# 05_RS485.net
KiCad netlist of a schematic drawn in Altium Designer
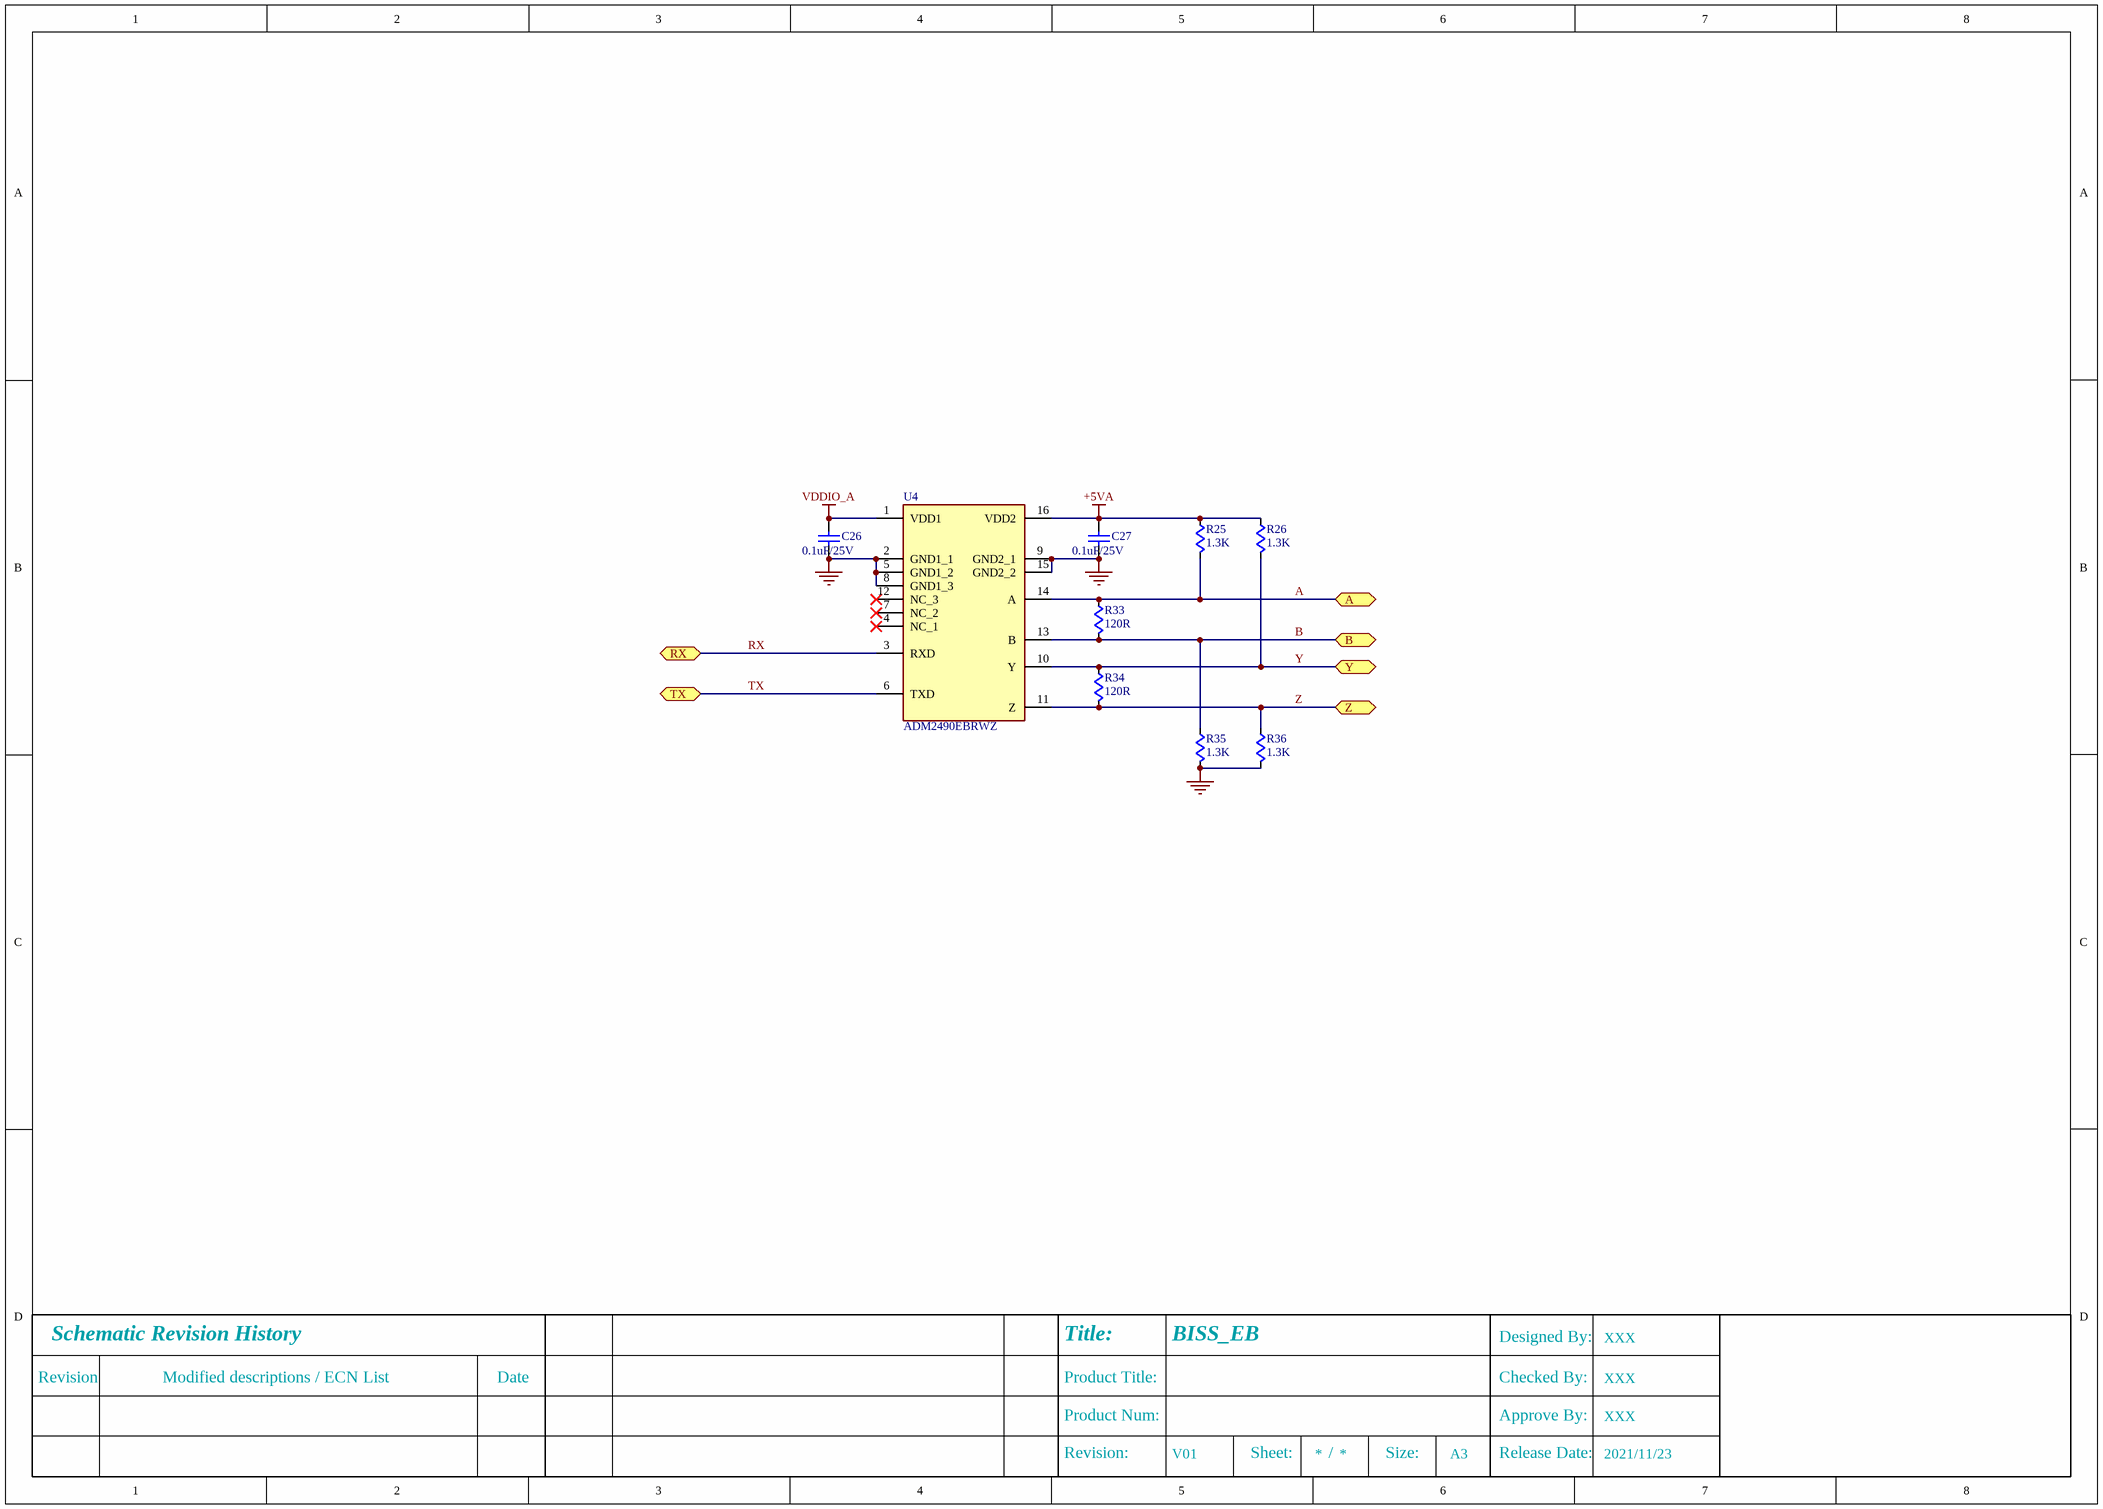
[diagram p0: 05_RS485.SchDoc]

(export (version "E")
  (design (tool "Eeschema 10.0.6"))
  (components
    (comp (ref "C26")
      (value "0.1uF/25V")
      (footprint "C0603")
      (description "MLCC")
      (libsource (lib "SamacSys") (part "C"))
    )
    (comp (ref "C27")
      (value "0.1uF/25V")
      (footprint "C0603")
      (description "MLCC")
      (libsource (lib "SamacSys") (part "C"))
    )
    (comp (ref "R25")
      (value "1.3K")
      (footprint "SamacSys:R0603")
      (description "贴片电阻")
      (libsource (lib "SamacSys") (part "R"))
    )
    (comp (ref "R26")
      (value "1.3K")
      (footprint "SamacSys:R0603")
      (description "贴片电阻")
      (libsource (lib "SamacSys") (part "R"))
    )
    (comp (ref "R33")
      (value "120R")
      (footprint "SamacSys:R0603")
      (description "贴片电阻")
      (libsource (lib "SamacSys") (part "R"))
    )
    (comp (ref "R34")
      (value "120R")
      (footprint "SamacSys:R0603")
      (description "贴片电阻")
      (libsource (lib "SamacSys") (part "R"))
    )
    (comp (ref "R35")
      (value "1.3K")
      (footprint "SamacSys:R0603")
      (description "贴片电阻")
      (libsource (lib "SamacSys") (part "R"))
    )
    (comp (ref "R36")
      (value "1.3K")
      (footprint "SamacSys:R0603")
      (description "贴片电阻")
      (libsource (lib "SamacSys") (part "R"))
    )
    (comp (ref "U4")
      (value "ADM2490EBRWZ")
      (footprint "SamacSys:SOIC127P1032X265-16N")
      (description "Integrated Circuit")
      (fields (field (name "MOUSER PART NUMBER") "584-ADM2490EBRWZ"))
      (libsource (lib "SamacSys") (part "ADM2490EBRWZ"))
    )
  )
  (nets
    (net (code "1") (name "+5VA") (class "Default")
      (node (ref "C27") (pin "1") (pinfunction "1_1") (pintype "passive"))
      (node (ref "R25") (pin "1") (pinfunction "1_1") (pintype "passive"))
      (node (ref "R26") (pin "1") (pinfunction "1_1") (pintype "passive"))
      (node (ref "U4") (pin "16") (pinfunction "VDD2_16") (pintype "passive"))
    )
    (net (code "2") (name "/A") (class "Default")
      (node (ref "R25") (pin "2") (pinfunction "2_2") (pintype "passive"))
      (node (ref "R33") (pin "1") (pinfunction "1_1") (pintype "passive"))
      (node (ref "U4") (pin "14") (pinfunction "A_14") (pintype "passive"))
    )
    (net (code "3") (name "/B") (class "Default")
      (node (ref "R33") (pin "2") (pinfunction "2_2") (pintype "passive"))
      (node (ref "R35") (pin "1") (pinfunction "1_1") (pintype "passive"))
      (node (ref "U4") (pin "13") (pinfunction "B_13") (pintype "passive"))
    )
    (net (code "4") (name "/RX") (class "Default")
      (node (ref "U4") (pin "3") (pinfunction "RXD_3") (pintype "passive"))
    )
    (net (code "5") (name "/TX") (class "Default")
      (node (ref "U4") (pin "6") (pinfunction "TXD_6") (pintype "passive"))
    )
    (net (code "6") (name "/Y") (class "Default")
      (node (ref "R26") (pin "2") (pinfunction "2_2") (pintype "passive"))
      (node (ref "R34") (pin "1") (pinfunction "1_1") (pintype "passive"))
      (node (ref "U4") (pin "10") (pinfunction "Y_10") (pintype "passive"))
    )
    (net (code "7") (name "/Z") (class "Default")
      (node (ref "R34") (pin "2") (pinfunction "2_2") (pintype "passive"))
      (node (ref "R36") (pin "1") (pinfunction "1_1") (pintype "passive"))
      (node (ref "U4") (pin "11") (pinfunction "Z_11") (pintype "passive"))
    )
    (net (code "8") (name "GND") (class "Default")
      (node (ref "C26") (pin "2") (pinfunction "2_2") (pintype "passive"))
      (node (ref "C27") (pin "2") (pinfunction "2_2") (pintype "passive"))
      (node (ref "R35") (pin "2") (pinfunction "2_2") (pintype "passive"))
      (node (ref "R36") (pin "2") (pinfunction "2_2") (pintype "passive"))
      (node (ref "U4") (pin "15") (pinfunction "GND2_2_15") (pintype "passive"))
      (node (ref "U4") (pin "2") (pinfunction "GND1_1_2") (pintype "passive"))
      (node (ref "U4") (pin "5") (pinfunction "GND1_2_5") (pintype "passive"))
      (node (ref "U4") (pin "8") (pinfunction "GND1_3_8") (pintype "passive"))
      (node (ref "U4") (pin "9") (pinfunction "GND2_1_9") (pintype "passive"))
    )
    (net (code "9") (name "VDDIO_A") (class "Default")
      (node (ref "C26") (pin "1") (pinfunction "1_1") (pintype "passive"))
      (node (ref "U4") (pin "1") (pinfunction "VDD1_1") (pintype "passive"))
    )
    (net (code "10") (name "unconnected-(U4-NC_1-Pad4)") (class "Default")
      (node (ref "U4") (pin "4") (pinfunction "NC_1_4") (pintype "passive+no_connect"))
    )
    (net (code "11") (name "unconnected-(U4-NC_2-Pad7)") (class "Default")
      (node (ref "U4") (pin "7") (pinfunction "NC_2_7") (pintype "passive+no_connect"))
    )
    (net (code "12") (name "unconnected-(U4-NC_3-Pad12)") (class "Default")
      (node (ref "U4") (pin "12") (pinfunction "NC_3_12") (pintype "passive+no_connect"))
    )
  )
)
